# usb_blaster.net
KiCad netlist of a schematic drawn in EAGLE
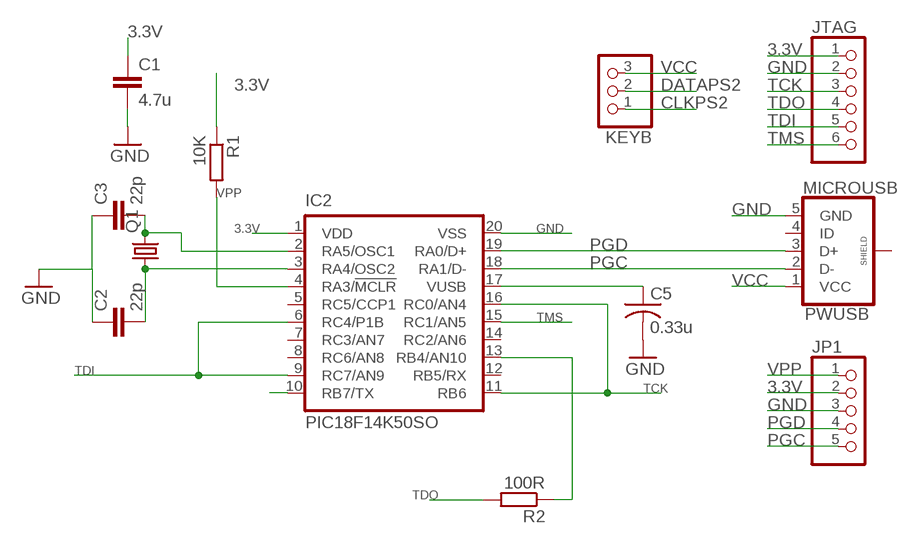
[diagram p0: schematic, sheet 1]

(export (version "E")
  (design (tool "Eeschema 10.0.6"))
  (components
    (comp (ref "C1")
      (value "4.7u")
      (footprint "eagle-import:C0805")
      (libsource (lib "eagle-import") (part "C-EUC0805"))
    )
    (comp (ref "C2")
      (value "22p")
      (footprint "eagle-import:C0805")
      (libsource (lib "eagle-import") (part "C-EUC0805"))
    )
    (comp (ref "C3")
      (value "22p")
      (footprint "eagle-import:C0805")
      (libsource (lib "eagle-import") (part "C-EUC0805"))
    )
    (comp (ref "C5")
      (value "0.33u")
      (footprint "eagle-import:C0805")
      (libsource (lib "eagle-import") (part "C-USC0805"))
    )
    (comp (ref "IC2")
      (value "PIC18F14K50SO")
      (footprint "eagle-import:SO20")
      (libsource (lib "eagle-import") (part "PIC18F14K50SO"))
    )
    (comp (ref "JP1")
      (value "PINHD-1X5")
      (footprint "eagle-import:1X05")
      (libsource (lib "eagle-import") (part "PINHD-1X5"))
    )
    (comp (ref "JTAG")
      (value "PINHD-1X6")
      (footprint "eagle-import:1X06")
      (libsource (lib "eagle-import") (part "PINHD-1X6"))
    )
    (comp (ref "KEYB")
      (value "PINHD-1X3")
      (footprint "eagle-import:1X03")
      (libsource (lib "eagle-import") (part "PINHD-1X3"))
    )
    (comp (ref "PWUSB")
      (value "MICROUSB")
      (footprint "eagle-import:MICRO_USB_1PRIMARY")
      (libsource (lib "eagle-import") (part "MICROUSB"))
    )
    (comp (ref "Q1")
      (value "CRYSTALHC49UP")
      (footprint "eagle-import:HC49UP")
      (libsource (lib "eagle-import") (part "CRYSTALHC49UP"))
    )
    (comp (ref "R1")
      (value "10K")
      (footprint "eagle-import:R0805")
      (libsource (lib "eagle-import") (part "R-EU_R0805"))
    )
    (comp (ref "R2")
      (value "100R")
      (footprint "eagle-import:R0805")
      (libsource (lib "eagle-import") (part "R-EU_R0805"))
    )
  )
  (nets
    (net (code "1") (name "/3.3V") (class "Default")
      (node (ref "C1") (pin "1") (pinfunction "1_1") (pintype "passive"))
      (node (ref "IC2") (pin "1") (pinfunction "VDD_1") (pintype "power_in"))
      (node (ref "JP1") (pin "2") (pinfunction "2_2") (pintype "passive"))
      (node (ref "JTAG") (pin "1") (pinfunction "1_1") (pintype "passive"))
      (node (ref "R1") (pin "1") (pinfunction "1_1") (pintype "passive"))
    )
    (net (code "2") (name "/CLKPS2") (class "Default")
      (node (ref "KEYB") (pin "1") (pinfunction "1_1") (pintype "passive"))
    )
    (net (code "3") (name "/DATAPS2") (class "Default")
      (node (ref "KEYB") (pin "2") (pinfunction "2_2") (pintype "passive"))
    )
    (net (code "4") (name "/PGC") (class "Default")
      (node (ref "IC2") (pin "18") (pinfunction "RA1/D-_18") (pintype "bidirectional"))
      (node (ref "JP1") (pin "5") (pinfunction "5_5") (pintype "passive"))
      (node (ref "PWUSB") (pin "2") (pinfunction "D-_2") (pintype "bidirectional"))
    )
    (net (code "5") (name "/PGD") (class "Default")
      (node (ref "IC2") (pin "19") (pinfunction "RA0/D+_19") (pintype "bidirectional"))
      (node (ref "JP1") (pin "4") (pinfunction "4_4") (pintype "passive"))
      (node (ref "PWUSB") (pin "3") (pinfunction "D+_3") (pintype "bidirectional"))
    )
    (net (code "6") (name "/TCK") (class "Default")
      (node (ref "IC2") (pin "11") (pinfunction "RB6_11") (pintype "bidirectional"))
      (node (ref "IC2") (pin "16") (pinfunction "RC0/AN4_16") (pintype "bidirectional"))
      (node (ref "JTAG") (pin "3") (pinfunction "3_3") (pintype "passive"))
    )
    (net (code "7") (name "/TDI") (class "Default")
      (node (ref "IC2") (pin "6") (pinfunction "RC4/P1B_6") (pintype "bidirectional"))
      (node (ref "IC2") (pin "9") (pinfunction "RC7/AN9_9") (pintype "bidirectional"))
      (node (ref "JTAG") (pin "5") (pinfunction "5_5") (pintype "passive"))
    )
    (net (code "8") (name "/TDO") (class "Default")
      (node (ref "JTAG") (pin "4") (pinfunction "4_4") (pintype "passive"))
      (node (ref "R2") (pin "2") (pinfunction "2_2") (pintype "passive"))
    )
    (net (code "9") (name "/TMS") (class "Default")
      (node (ref "IC2") (pin "15") (pinfunction "RC1/AN5_15") (pintype "bidirectional"))
      (node (ref "JTAG") (pin "6") (pinfunction "6_6") (pintype "passive"))
    )
    (net (code "10") (name "/VCC") (class "Default")
      (node (ref "KEYB") (pin "3") (pinfunction "3_3") (pintype "passive"))
      (node (ref "PWUSB") (pin "1") (pinfunction "VCC_1") (pintype "bidirectional"))
    )
    (net (code "11") (name "/VPP") (class "Default")
      (node (ref "IC2") (pin "4") (pinfunction "RA3/~{MCLR}_4") (pintype "bidirectional"))
      (node (ref "JP1") (pin "1") (pinfunction "1_1") (pintype "passive"))
      (node (ref "R1") (pin "2") (pinfunction "2_2") (pintype "passive"))
    )
    (net (code "12") (name "GND") (class "Default")
      (node (ref "C1") (pin "2") (pinfunction "2_2") (pintype "passive"))
      (node (ref "C2") (pin "1") (pinfunction "1_1") (pintype "passive"))
      (node (ref "C3") (pin "1") (pinfunction "1_1") (pintype "passive"))
      (node (ref "C5") (pin "2") (pinfunction "2_2") (pintype "passive"))
      (node (ref "IC2") (pin "20") (pinfunction "VSS_20") (pintype "power_in"))
      (node (ref "JP1") (pin "3") (pinfunction "3_3") (pintype "passive"))
      (node (ref "JTAG") (pin "2") (pinfunction "2_2") (pintype "passive"))
      (node (ref "PWUSB") (pin "5") (pinfunction "GND_5") (pintype "bidirectional"))
    )
    (net (code "13") (name "Net-(IC2-RA4{slash}OSC2)") (class "Default")
      (node (ref "C2") (pin "2") (pinfunction "2_2") (pintype "passive"))
      (node (ref "IC2") (pin "3") (pinfunction "RA4/OSC2_3") (pintype "bidirectional"))
      (node (ref "Q1") (pin "1") (pinfunction "1_1") (pintype "passive"))
    )
    (net (code "14") (name "Net-(IC2-RA5{slash}OSC1)") (class "Default")
      (node (ref "C3") (pin "2") (pinfunction "2_2") (pintype "passive"))
      (node (ref "IC2") (pin "2") (pinfunction "RA5/OSC1_2") (pintype "bidirectional"))
      (node (ref "Q1") (pin "2") (pinfunction "2_2") (pintype "passive"))
    )
    (net (code "15") (name "Net-(IC2-RB4{slash}AN10)") (class "Default")
      (node (ref "IC2") (pin "13") (pinfunction "RB4/AN10_13") (pintype "bidirectional"))
      (node (ref "R2") (pin "1") (pinfunction "1_1") (pintype "passive"))
    )
    (net (code "16") (name "Net-(IC2-VUSB)") (class "Default")
      (node (ref "C5") (pin "1") (pinfunction "1_1") (pintype "passive"))
      (node (ref "IC2") (pin "17") (pinfunction "VUSB_17") (pintype "bidirectional"))
    )
    (net (code "17") (name "unconnected-(IC2-RB5{slash}RX-Pad12)") (class "Default")
      (node (ref "IC2") (pin "12") (pinfunction "RB5/RX_12") (pintype "bidirectional"))
    )
    (net (code "18") (name "unconnected-(IC2-RB7{slash}TX-Pad10)") (class "Default")
      (node (ref "IC2") (pin "10") (pinfunction "RB7/TX_10") (pintype "bidirectional"))
    )
    (net (code "19") (name "unconnected-(IC2-RC2{slash}AN6-Pad14)") (class "Default")
      (node (ref "IC2") (pin "14") (pinfunction "RC2/AN6_14") (pintype "bidirectional"))
    )
    (net (code "20") (name "unconnected-(IC2-RC3{slash}AN7-Pad7)") (class "Default")
      (node (ref "IC2") (pin "7") (pinfunction "RC3/AN7_7") (pintype "bidirectional"))
    )
    (net (code "21") (name "unconnected-(IC2-RC5{slash}CCP1-Pad5)") (class "Default")
      (node (ref "IC2") (pin "5") (pinfunction "RC5/CCP1_5") (pintype "bidirectional"))
    )
    (net (code "22") (name "unconnected-(IC2-RC6{slash}AN8-Pad8)") (class "Default")
      (node (ref "IC2") (pin "8") (pinfunction "RC6/AN8_8") (pintype "bidirectional"))
    )
    (net (code "23") (name "unconnected-(PWUSB-ID-Pad4)") (class "Default")
      (node (ref "PWUSB") (pin "4") (pinfunction "ID_4") (pintype "bidirectional"))
    )
    (net (code "24") (name "unconnected-(PWUSB-SHIELD-Pad6)") (class "Default")
      (node (ref "PWUSB") (pin "6") (pinfunction "SHIELD_6") (pintype "bidirectional"))
    )
  )
)
